# MICRO_AND_VREF.net
KiCad netlist of a schematic drawn in Altium Designer
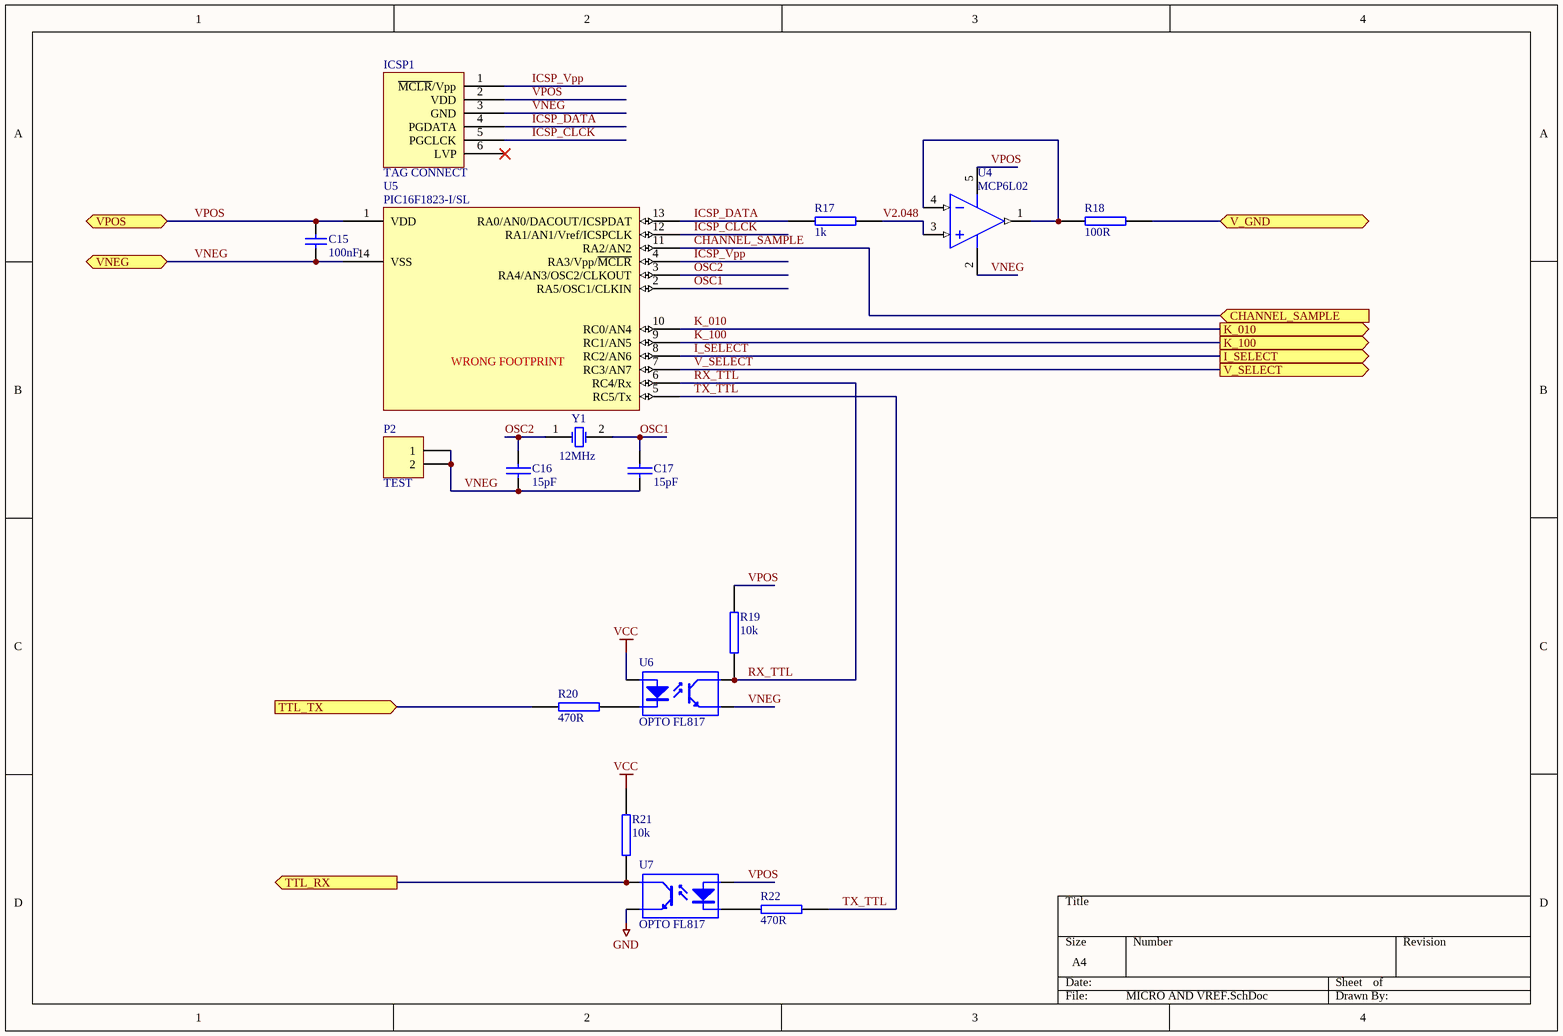
[diagram p0: MICRO AND VREF.SchDoc]

(export (version "E")
  (design (tool "Eeschema 10.0.6"))
  (components
    (comp (ref "C15")
      (value "100nF")
      (footprint "CAP (3D) - 0603")
      (description "Capacitor")
      (libsource (lib "Miscellaneous Devices") (part "Cap"))
    )
    (comp (ref "C16")
      (value "15pF")
      (footprint "CAP (3D) - 0603")
      (description "CAPACITOR SMD 0402")
      (fields (field (name "MOUSER PART NO.") "140-CC504N150J-RC") (field (name "MANUFACTURER") "Xicon"))
      (libsource (lib "401 CCPA") (part "CAP"))
    )
    (comp (ref "C17")
      (value "15pF")
      (footprint "CAP (3D) - 0603")
      (description "CAPACITOR SMD 0402")
      (fields (field (name "MOUSER PART NO.") "140-CC504N150J-RC") (field (name "MANUFACTURER") "Xicon"))
      (libsource (lib "401 CCPA") (part "CAP"))
    )
    (comp (ref "ICSP1")
      (value "TAG CONNECT")
      (footprint "ICSP - TAG CONNECT TYPE2")
      (fields (field (name "MANUFACTURER") "N/A - PCB ARTWORK"))
      (libsource (lib "I2C PENDANT") (part "ICSP - TAG CONNECT"))
    )
    (comp (ref "P2")
      (value "TEST")
      (footprint "HDR1X2")
      (description "Header, 2-Pin")
      (fields
        (field (name "MANUFACTURER") "Bourns")
        (field (name "MANUFACTURER PART NO.") "CR0603-FX-5900ELF")
      )
      (libsource (lib "Miscellaneous Connectors") (part "Header 2"))
    )
    (comp (ref "R17")
      (value "1k")
      (footprint "RES (3D) - 0603")
      (description "RESISTOR SMD 0603 1k")
      (libsource (lib "NASCO Resistors") (part "RES SMD 0603 1k"))
    )
    (comp (ref "R18")
      (value "100R")
      (footprint "RES (3D) - 0603")
      (description "RESISTOR SMD 0603")
      (libsource (lib "NASCO") (part "RES SMD 0603"))
    )
    (comp (ref "R19")
      (value "10k")
      (footprint "RES (3D) - 0603")
      (description "RESISTOR SMD 0603")
      (libsource (lib "NASCO Resistors") (part "RES SMD 0603 100R"))
    )
    (comp (ref "R20")
      (value "470R")
      (footprint "RES (3D) - 0603")
      (description "RESISTOR SMD 0603 1k")
      (libsource (lib "NASCO Resistors") (part "RES SMD 0603 1k"))
    )
    (comp (ref "R21")
      (value "10k")
      (footprint "RES (3D) - 0603")
      (description "RESISTOR SMD 0603")
      (libsource (lib "NASCO Resistors") (part "RES SMD 0603 100R"))
    )
    (comp (ref "R22")
      (value "470R")
      (footprint "RES (3D) - 0603")
      (description "RESISTOR SMD 0603 1k")
      (libsource (lib "NASCO Resistors") (part "RES SMD 0603 1k"))
    )
    (comp (ref "U4")
      (value "MCP6L02")
      (footprint "SOT23-5AL")
      (description "MCP6L01")
      (libsource (lib "Schlib1") (part "MCP6L01"))
    )
    (comp (ref "U5")
      (value "PIC16F1823-I/SL")
      (footprint "SOIC-14")
      (libsource (lib "*") (part "PIC16F1823"))
    )
    (comp (ref "U6")
      (value "OPTO FL817")
      (footprint "DIP_4")
      (description "4-Pin Phototransistor Optocoupler")
      (libsource (lib "Schlib1") (part "FL817"))
    )
    (comp (ref "U7")
      (value "OPTO FL817")
      (footprint "DIP_4")
      (description "4-Pin Phototransistor Optocoupler")
      (libsource (lib "Schlib1") (part "FL817"))
    )
    (comp (ref "Y1")
      (value "12MHz")
      (footprint "CRYSTAL 3x8")
      (description "Crystal Oscillator")
      (fields (field (name "Comment") "XTAL"))
      (libsource (lib "Miscellaneous Devices") (part "XTAL"))
    )
  )
  (nets
    (net (code "1") (name "/CHANNEL_SAMPLE") (class "Default")
      (node (ref "U5") (pin "11") (pinfunction "RA2/AN2_11") (pintype "bidirectional"))
    )
    (net (code "2") (name "/ICSP_CLCK") (class "Default")
      (node (ref "ICSP1") (pin "5") (pinfunction "PGCLCK_5") (pintype "passive"))
      (node (ref "U5") (pin "12") (pinfunction "RA1/AN1/Vref/ICSPCLK_12") (pintype "bidirectional"))
    )
    (net (code "3") (name "/ICSP_DATA") (class "Default")
      (node (ref "ICSP1") (pin "4") (pinfunction "PGDATA_4") (pintype "passive"))
      (node (ref "R17") (pin "2") (pinfunction "2_2") (pintype "passive"))
      (node (ref "U5") (pin "13") (pinfunction "RA0/AN0/DACOUT/ICSPDAT_13") (pintype "bidirectional"))
    )
    (net (code "4") (name "/ICSP_Vpp") (class "Default")
      (node (ref "ICSP1") (pin "1") (pinfunction "~{MCLR}/Vpp_1") (pintype "passive"))
      (node (ref "U5") (pin "4") (pinfunction "RA3/Vpp/~{MCLR}_4") (pintype "bidirectional"))
    )
    (net (code "5") (name "/I_SELECT") (class "Default")
      (node (ref "U5") (pin "8") (pinfunction "RC2/AN6_8") (pintype "bidirectional"))
    )
    (net (code "6") (name "/K_010") (class "Default")
      (node (ref "U5") (pin "10") (pinfunction "RC0/AN4_10") (pintype "bidirectional"))
    )
    (net (code "7") (name "/K_100") (class "Default")
      (node (ref "U5") (pin "9") (pinfunction "RC1/AN5_9") (pintype "bidirectional"))
    )
    (net (code "8") (name "/OSC1") (class "Default")
      (node (ref "C17") (pin "1") (pinfunction "1_1") (pintype "passive"))
      (node (ref "U5") (pin "2") (pinfunction "RA5/OSC1/CLKIN_2") (pintype "bidirectional"))
      (node (ref "Y1") (pin "2") (pinfunction "OSC2_2") (pintype "passive"))
    )
    (net (code "9") (name "/OSC2") (class "Default")
      (node (ref "C16") (pin "1") (pinfunction "1_1") (pintype "passive"))
      (node (ref "U5") (pin "3") (pinfunction "RA4/AN3/OSC2/CLKOUT_3") (pintype "bidirectional"))
      (node (ref "Y1") (pin "1") (pinfunction "OSC1_1") (pintype "passive"))
    )
    (net (code "10") (name "/RX_TTL") (class "Default")
      (node (ref "R19") (pin "2") (pinfunction "2_2") (pintype "passive"))
      (node (ref "U5") (pin "6") (pinfunction "RC4/Rx_6") (pintype "bidirectional"))
      (node (ref "U6") (pin "4") (pinfunction "C_4") (pintype "passive"))
    )
    (net (code "11") (name "/TTL_RX") (class "Default")
      (node (ref "R21") (pin "2") (pinfunction "2_2") (pintype "passive"))
      (node (ref "U7") (pin "4") (pinfunction "C_4") (pintype "passive"))
    )
    (net (code "12") (name "/TTL_TX") (class "Default")
      (node (ref "R20") (pin "1") (pinfunction "1_1") (pintype "passive"))
    )
    (net (code "13") (name "/TX_TTL") (class "Default")
      (node (ref "R22") (pin "2") (pinfunction "2_2") (pintype "passive"))
      (node (ref "U5") (pin "5") (pinfunction "RC5/Tx_5") (pintype "bidirectional"))
    )
    (net (code "14") (name "/V2.048") (class "Default")
      (node (ref "R17") (pin "1") (pinfunction "1_1") (pintype "passive"))
      (node (ref "U4") (pin "3") (pinfunction "INA+_3") (pintype "input"))
    )
    (net (code "15") (name "/VNEG") (class "Default")
      (node (ref "C15") (pin "1") (pinfunction "1_1") (pintype "passive"))
      (node (ref "C16") (pin "2") (pinfunction "2_2") (pintype "passive"))
      (node (ref "C17") (pin "2") (pinfunction "2_2") (pintype "passive"))
      (node (ref "ICSP1") (pin "3") (pinfunction "GND_3") (pintype "passive"))
      (node (ref "P2") (pin "1") (pinfunction "1_1") (pintype "passive"))
      (node (ref "P2") (pin "2") (pinfunction "2_2") (pintype "passive"))
      (node (ref "U4") (pin "2") (pinfunction "GND_2") (pintype "power_in"))
      (node (ref "U5") (pin "14") (pinfunction "VSS_14") (pintype "power_in"))
      (node (ref "U6") (pin "3") (pinfunction "E_3") (pintype "passive"))
    )
    (net (code "16") (name "/VPOS") (class "Default")
      (node (ref "C15") (pin "2") (pinfunction "2_2") (pintype "passive"))
      (node (ref "ICSP1") (pin "2") (pinfunction "VDD_2") (pintype "passive"))
      (node (ref "R19") (pin "1") (pinfunction "1_1") (pintype "passive"))
      (node (ref "U4") (pin "5") (pinfunction "V+_5") (pintype "power_in"))
      (node (ref "U5") (pin "1") (pinfunction "VDD_1") (pintype "power_in"))
      (node (ref "U7") (pin "1") (pinfunction "A_1") (pintype "passive"))
    )
    (net (code "17") (name "/V_GND") (class "Default")
      (node (ref "R18") (pin "2") (pinfunction "2_2") (pintype "passive"))
    )
    (net (code "18") (name "/V_SELECT") (class "Default")
      (node (ref "U5") (pin "7") (pinfunction "RC3/AN7_7") (pintype "bidirectional"))
    )
    (net (code "19") (name "GND") (class "Default")
      (node (ref "U7") (pin "3") (pinfunction "E_3") (pintype "passive"))
    )
    (net (code "20") (name "Net-(U4-INA-)") (class "Default")
      (node (ref "R18") (pin "1") (pinfunction "1_1") (pintype "passive"))
      (node (ref "U4") (pin "1") (pinfunction "OUTA_1") (pintype "output"))
      (node (ref "U4") (pin "4") (pinfunction "INA-_4") (pintype "input"))
    )
    (net (code "21") (name "Net-(U6-K)") (class "Default")
      (node (ref "R20") (pin "2") (pinfunction "2_2") (pintype "passive"))
      (node (ref "U6") (pin "2") (pinfunction "K_2") (pintype "passive"))
    )
    (net (code "22") (name "Net-(U7-K)") (class "Default")
      (node (ref "R22") (pin "1") (pinfunction "1_1") (pintype "passive"))
      (node (ref "U7") (pin "2") (pinfunction "K_2") (pintype "passive"))
    )
    (net (code "23") (name "VCC") (class "Default")
      (node (ref "R21") (pin "1") (pinfunction "1_1") (pintype "passive"))
      (node (ref "U6") (pin "1") (pinfunction "A_1") (pintype "passive"))
    )
    (net (code "24") (name "unconnected-(ICSP1-LVP-Pad6)") (class "Default")
      (node (ref "ICSP1") (pin "6") (pinfunction "LVP_6") (pintype "passive+no_connect"))
    )
  )
)
